# ESP_Updater.net
KiCad netlist of a schematic drawn in EAGLE
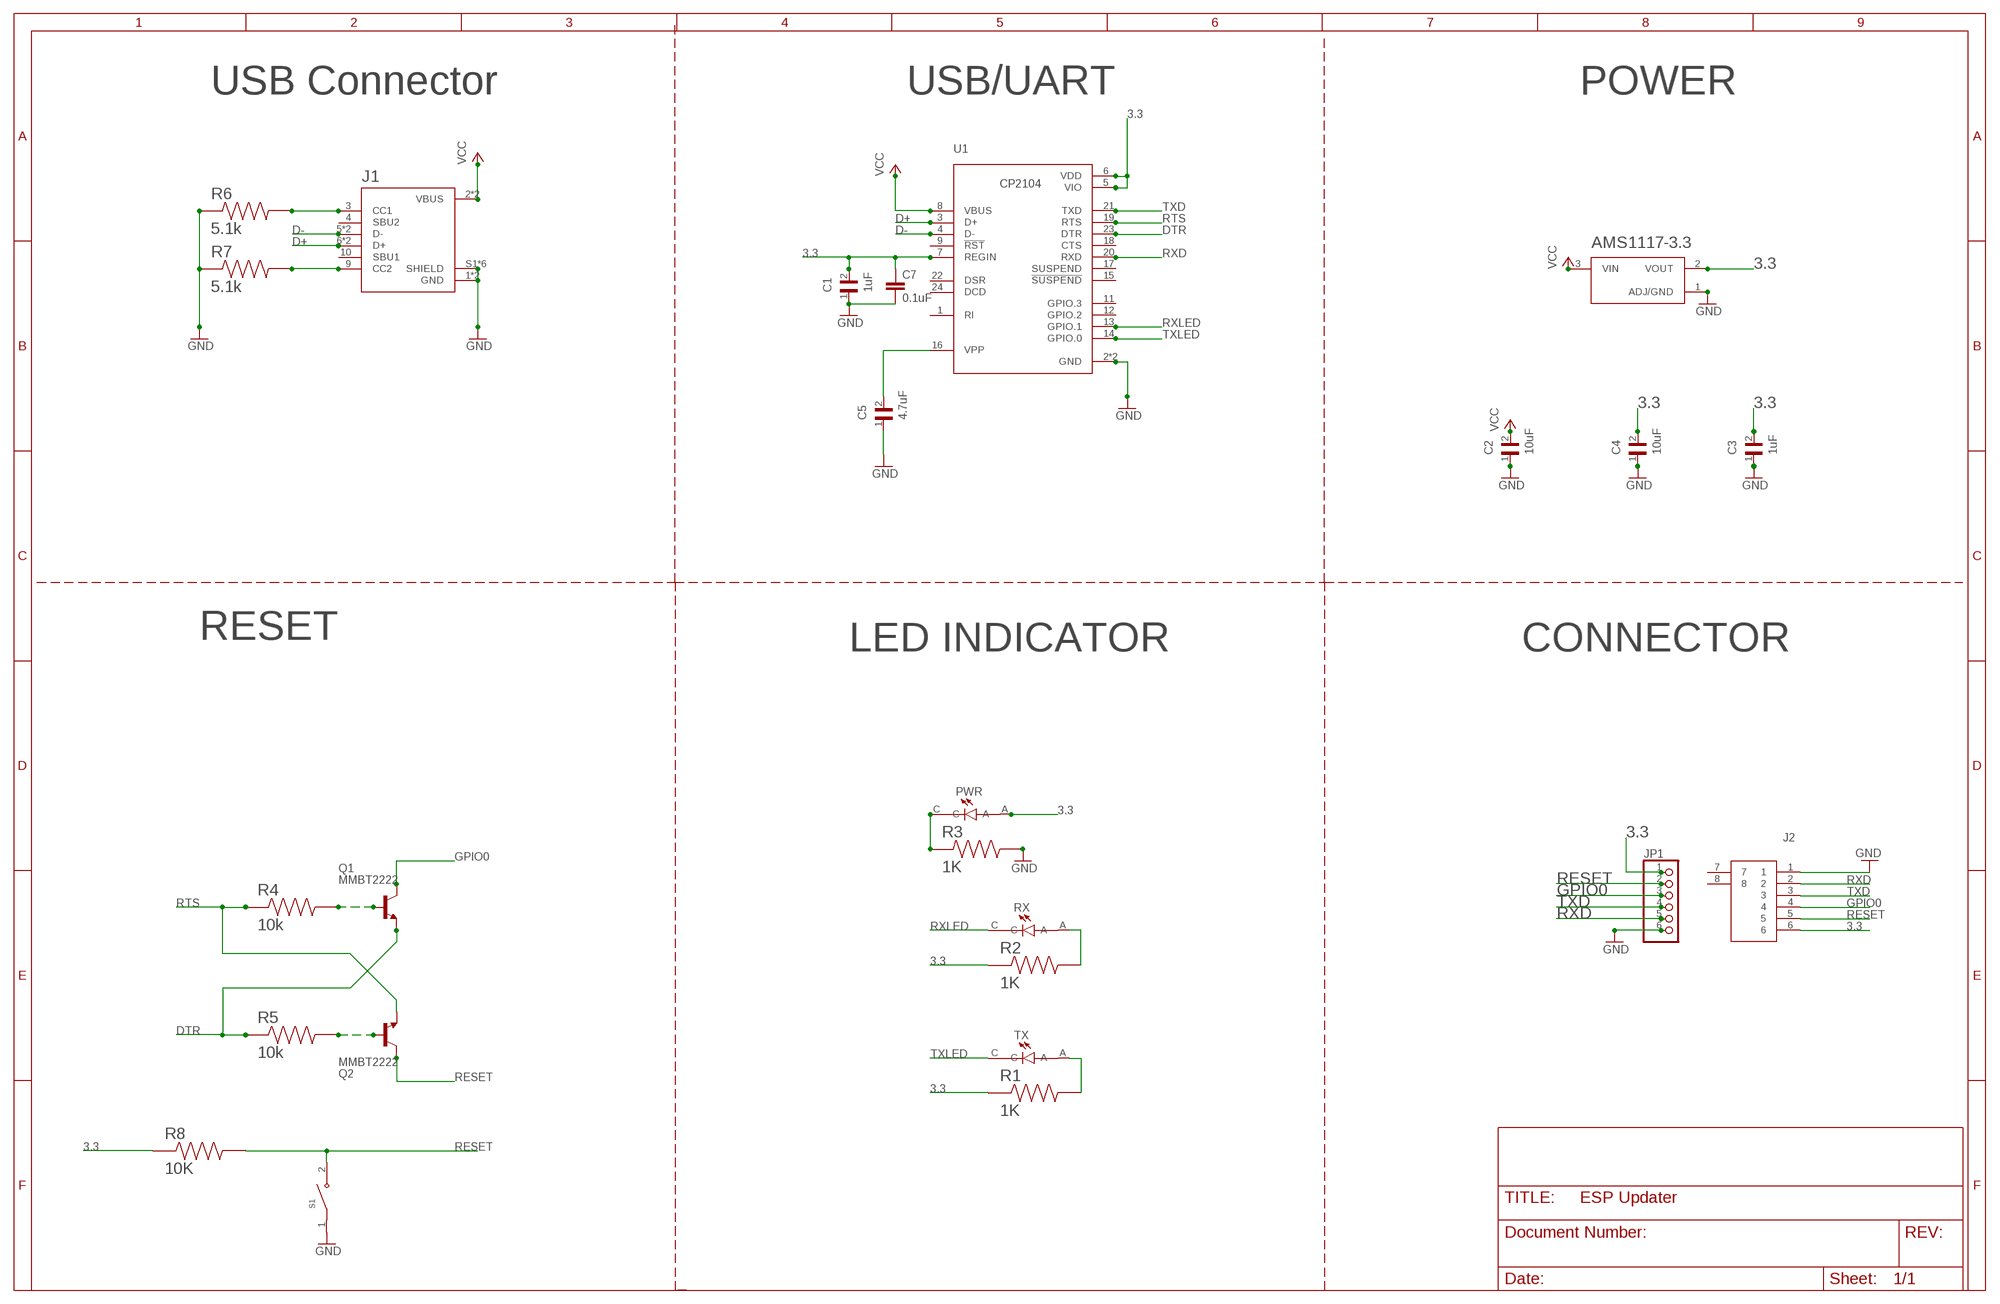
[diagram p0: schematic, sheet 1]

(export (version "E")
  (design (tool "Eeschema 10.0.6"))
  (components
    (comp (ref "C1")
      (value "1uF")
      (footprint "eagle-import:CAPC2012X94N")
      (fields (field (name "MF") "AVX") (field (name "MP") "0805YC103J4T2A"))
      (libsource (lib "eagle-import") (part "0805YC103J4T2A"))
    )
    (comp (ref "C2")
      (value "10uF")
      (footprint "eagle-import:CAPC2012X94N")
      (fields (field (name "MF") "AVX") (field (name "MP") "0805YC103J4T2A"))
      (libsource (lib "eagle-import") (part "0805YC103J4T2A"))
    )
    (comp (ref "C3")
      (value "1uF")
      (footprint "eagle-import:CAPC2012X94N")
      (fields (field (name "MF") "AVX") (field (name "MP") "0805YC103J4T2A"))
      (libsource (lib "eagle-import") (part "0805YC103J4T2A"))
    )
    (comp (ref "C4")
      (value "10uF")
      (footprint "eagle-import:CAPC2012X94N")
      (fields (field (name "MF") "AVX") (field (name "MP") "0805YC103J4T2A"))
      (libsource (lib "eagle-import") (part "0805YC103J4T2A"))
    )
    (comp (ref "C5")
      (value "4.7uF")
      (footprint "eagle-import:CAPC2012X94N")
      (fields (field (name "MF") "AVX") (field (name "MP") "0805YC103J4T2A"))
      (libsource (lib "eagle-import") (part "0805YC103J4T2A"))
    )
    (comp (ref "C7")
      (value "0.1uF")
      (footprint "eagle-import:C0603")
      (libsource (lib "eagle-import") (part "C-EUC0603"))
    )
    (comp (ref "J1")
      (value "DX07S016JA1R1500")
      (footprint "eagle-import:JAE_DX07S016JA1R1500")
      (fields (field (name "MF") "JAE Electronics"))
      (libsource (lib "eagle-import") (part "DX07S016JA1R1500"))
    )
    (comp (ref "J2")
      (value "52852-0670")
      (footprint "eagle-import:528520670")
      (fields (field (name "MOUSER_PART_NUMBER") "538-52852-0670"))
      (libsource (lib "eagle-import") (part "52852-0670"))
    )
    (comp (ref "JP1")
      (value "PINHD-1X6")
      (footprint "eagle-import:1X06")
      (libsource (lib "eagle-import") (part "PINHD-1X6"))
    )
    (comp (ref "PWR")
      (value "SML-LXT0805IW-TR")
      (footprint "eagle-import:LEDC2012X120N")
      (fields (field (name "MF") "Lumex Opto/Components"))
      (libsource (lib "eagle-import") (part "SML-LXT0805IW-TR"))
    )
    (comp (ref "Q1")
      (value "MMBT2222")
      (footprint "eagle-import:SOT23-BEC")
      (fields (field (name "MF") "ON Semiconductor"))
      (libsource (lib "eagle-import") (part "MMBT2222"))
    )
    (comp (ref "Q2")
      (value "MMBT2222")
      (footprint "eagle-import:SOT23-BEC")
      (fields (field (name "MF") "ON Semiconductor"))
      (libsource (lib "eagle-import") (part "MMBT2222"))
    )
    (comp (ref "R1")
      (value "1K")
      (footprint "eagle-import:RESC2012X60N")
      (fields (field (name "MF") "Yageo") (field (name "MP") "RC0805FR-07330RL"))
      (libsource (lib "eagle-import") (part "RC0805FR-07330RL"))
    )
    (comp (ref "R2")
      (value "1K")
      (footprint "eagle-import:RESC2012X60N")
      (fields (field (name "MF") "Yageo") (field (name "MP") "RC0805FR-07330RL"))
      (libsource (lib "eagle-import") (part "RC0805FR-07330RL"))
    )
    (comp (ref "R3")
      (value "1K")
      (footprint "eagle-import:RESC2012X60N")
      (fields (field (name "MF") "Yageo") (field (name "MP") "RC0805FR-07330RL"))
      (libsource (lib "eagle-import") (part "RC0805FR-07330RL"))
    )
    (comp (ref "R4")
      (value "10k")
      (footprint "eagle-import:RESC2012X60N")
      (fields (field (name "MF") "Yageo") (field (name "MP") "RC0805FR-07330RL"))
      (libsource (lib "eagle-import") (part "RC0805FR-07330RL"))
    )
    (comp (ref "R5")
      (value "10k")
      (footprint "eagle-import:RESC2012X60N")
      (fields (field (name "MF") "Yageo") (field (name "MP") "RC0805FR-07330RL"))
      (libsource (lib "eagle-import") (part "RC0805FR-07330RL"))
    )
    (comp (ref "R6")
      (value "5.1k")
      (footprint "eagle-import:RESC2012X60N")
      (fields (field (name "MF") "Yageo") (field (name "MP") "RC0805FR-07330RL"))
      (libsource (lib "eagle-import") (part "RC0805FR-07330RL"))
    )
    (comp (ref "R7")
      (value "5.1k")
      (footprint "eagle-import:RESC2012X60N")
      (fields (field (name "MF") "Yageo") (field (name "MP") "RC0805FR-07330RL"))
      (libsource (lib "eagle-import") (part "RC0805FR-07330RL"))
    )
    (comp (ref "R8")
      (value "10K")
      (footprint "eagle-import:RESC2012X60N")
      (fields (field (name "MF") "Yageo") (field (name "MP") "RC0805FR-07330RL"))
      (libsource (lib "eagle-import") (part "RC0805FR-07330RL"))
    )
    (comp (ref "RX")
      (value "SML-LXT0805IW-TR")
      (footprint "eagle-import:LEDC2012X120N")
      (fields (field (name "MF") "Lumex Opto/Components"))
      (libsource (lib "eagle-import") (part "SML-LXT0805IW-TR"))
    )
    (comp (ref "S1")
      (value "PTS636_SM43J_SMTR_LFS")
      (footprint "eagle-import:SW_PTS636_SM43J_SMTR_LFS")
      (fields (field (name "MF") "C&K") (field (name "MP") "PTS636 SM43J SMTR LFS"))
      (libsource (lib "eagle-import") (part "PTS636_SM43J_SMTR_LFS"))
    )
    (comp (ref "TX")
      (value "SML-LXT0805IW-TR")
      (footprint "eagle-import:LEDC2012X120N")
      (fields (field (name "MF") "Lumex Opto/Components"))
      (libsource (lib "eagle-import") (part "SML-LXT0805IW-TR"))
    )
    (comp (ref "U1")
      (value "CP2104")
      (footprint "eagle-import:QFN50P400X400X80-25N")
      (fields (field (name "MF") "Silicon Labs") (field (name "MP") "CP2104-F03-GM"))
      (libsource (lib "eagle-import") (part "CP2104-F03-GM"))
    )
    (comp (ref "U2")
      (value "AMS1117-3.3")
      (footprint "eagle-import:SOT229P700X180-4N")
      (fields (field (name "MF") "Advanced Monolithic Systems"))
      (libsource (lib "eagle-import") (part "AMS1117-3.3"))
    )
  )
  (nets
    (net (code "1") (name "/3.3") (class "Default")
      (node (ref "C1") (pin "2") (pinfunction "2_2") (pintype "passive"))
      (node (ref "C3") (pin "2") (pinfunction "2_2") (pintype "passive"))
      (node (ref "C4") (pin "2") (pinfunction "2_2") (pintype "passive"))
      (node (ref "C7") (pin "1") (pinfunction "1_1") (pintype "passive"))
      (node (ref "J2") (pin "6") (pinfunction "6_6") (pintype "bidirectional"))
      (node (ref "JP1") (pin "1") (pinfunction "1_1") (pintype "passive"))
      (node (ref "PWR") (pin "A") (pinfunction "A_A") (pintype "passive"))
      (node (ref "R1") (pin "1") (pinfunction "1_1") (pintype "passive"))
      (node (ref "R2") (pin "1") (pinfunction "1_1") (pintype "passive"))
      (node (ref "R8") (pin "1") (pinfunction "1_1") (pintype "passive"))
      (node (ref "U1") (pin "5") (pinfunction "VIO_5") (pintype "power_in"))
      (node (ref "U1") (pin "6") (pinfunction "VDD_6") (pintype "power_in"))
      (node (ref "U1") (pin "7") (pinfunction "REGIN_7") (pintype "input"))
      (node (ref "U2") (pin "2") (pinfunction "VOUT_2") (pintype "output"))
    )
    (net (code "2") (name "/D+") (class "Default")
      (node (ref "J1") (pin "6") (pinfunction "D+_6") (pintype "passive"))
      (node (ref "J1") (pin "7") (pinfunction "D+_7") (pintype "passive"))
      (node (ref "U1") (pin "3") (pinfunction "D+_3") (pintype "bidirectional"))
    )
    (net (code "3") (name "/D-") (class "Default")
      (node (ref "J1") (pin "5") (pinfunction "D-_5") (pintype "passive"))
      (node (ref "J1") (pin "8") (pinfunction "D-_8") (pintype "passive"))
      (node (ref "U1") (pin "4") (pinfunction "D-_4") (pintype "bidirectional"))
    )
    (net (code "4") (name "/DTR") (class "Default")
      (node (ref "Q1") (pin "E") (pinfunction "E_E") (pintype "passive"))
      (node (ref "R5") (pin "1") (pinfunction "1_1") (pintype "passive"))
      (node (ref "U1") (pin "23") (pinfunction "DTR_23") (pintype "output"))
    )
    (net (code "5") (name "/GPIO0") (class "Default")
      (node (ref "J2") (pin "4") (pinfunction "4_4") (pintype "bidirectional"))
      (node (ref "JP1") (pin "3") (pinfunction "3_3") (pintype "passive"))
      (node (ref "Q1") (pin "C") (pinfunction "C_C") (pintype "passive"))
    )
    (net (code "6") (name "/RESET") (class "Default")
      (node (ref "J2") (pin "5") (pinfunction "5_5") (pintype "bidirectional"))
      (node (ref "JP1") (pin "2") (pinfunction "2_2") (pintype "passive"))
      (node (ref "Q2") (pin "C") (pinfunction "C_C") (pintype "passive"))
      (node (ref "R8") (pin "2") (pinfunction "2_2") (pintype "passive"))
      (node (ref "S1") (pin "2") (pinfunction "NO_2") (pintype "passive"))
    )
    (net (code "7") (name "/RTS") (class "Default")
      (node (ref "Q2") (pin "E") (pinfunction "E_E") (pintype "passive"))
      (node (ref "R4") (pin "1") (pinfunction "1_1") (pintype "passive"))
      (node (ref "U1") (pin "19") (pinfunction "RTS_19") (pintype "output"))
    )
    (net (code "8") (name "/RXD") (class "Default")
      (node (ref "J2") (pin "2") (pinfunction "2_2") (pintype "bidirectional"))
      (node (ref "JP1") (pin "5") (pinfunction "5_5") (pintype "passive"))
      (node (ref "U1") (pin "20") (pinfunction "RXD_20") (pintype "input"))
    )
    (net (code "9") (name "/RXLED") (class "Default")
      (node (ref "RX") (pin "C") (pinfunction "C_C") (pintype "passive"))
      (node (ref "U1") (pin "13") (pinfunction "GPIO.1_13") (pintype "bidirectional"))
    )
    (net (code "10") (name "/TXD") (class "Default")
      (node (ref "J2") (pin "3") (pinfunction "3_3") (pintype "bidirectional"))
      (node (ref "JP1") (pin "4") (pinfunction "4_4") (pintype "passive"))
      (node (ref "U1") (pin "21") (pinfunction "TXD_21") (pintype "output"))
    )
    (net (code "11") (name "/TXLED") (class "Default")
      (node (ref "TX") (pin "C") (pinfunction "C_C") (pintype "passive"))
      (node (ref "U1") (pin "14") (pinfunction "GPIO.0_14") (pintype "bidirectional"))
    )
    (net (code "12") (name "GND") (class "Default")
      (node (ref "C1") (pin "1") (pinfunction "1_1") (pintype "passive"))
      (node (ref "C2") (pin "1") (pinfunction "1_1") (pintype "passive"))
      (node (ref "C3") (pin "1") (pinfunction "1_1") (pintype "passive"))
      (node (ref "C4") (pin "1") (pinfunction "1_1") (pintype "passive"))
      (node (ref "C5") (pin "1") (pinfunction "1_1") (pintype "passive"))
      (node (ref "C7") (pin "2") (pinfunction "2_2") (pintype "passive"))
      (node (ref "J1") (pin "1") (pinfunction "GND_1") (pintype "power_in"))
      (node (ref "J1") (pin "12") (pinfunction "GND_12") (pintype "power_in"))
      (node (ref "J1") (pin "S1") (pinfunction "SHIELD_S1") (pintype "passive"))
      (node (ref "J1") (pin "S2") (pinfunction "SHIELD_S2") (pintype "passive"))
      (node (ref "J1") (pin "S3") (pinfunction "SHIELD_S3") (pintype "passive"))
      (node (ref "J1") (pin "S4") (pinfunction "SHIELD_S4") (pintype "passive"))
      (node (ref "J1") (pin "S5") (pinfunction "SHIELD_S5") (pintype "passive"))
      (node (ref "J1") (pin "S6") (pinfunction "SHIELD_S6") (pintype "passive"))
      (node (ref "J2") (pin "1") (pinfunction "1_1") (pintype "bidirectional"))
      (node (ref "JP1") (pin "6") (pinfunction "6_6") (pintype "passive"))
      (node (ref "R3") (pin "2") (pinfunction "2_2") (pintype "passive"))
      (node (ref "R6") (pin "1") (pinfunction "1_1") (pintype "passive"))
      (node (ref "R7") (pin "1") (pinfunction "1_1") (pintype "passive"))
      (node (ref "S1") (pin "1") (pinfunction "COM_1") (pintype "passive"))
      (node (ref "U1") (pin "2") (pinfunction "GND_2") (pintype "power_in"))
      (node (ref "U1") (pin "25") (pinfunction "GND_25") (pintype "power_in"))
      (node (ref "U2") (pin "1") (pinfunction "ADJ/GND_1") (pintype "power_in"))
    )
    (net (code "13") (name "Net-(J1-CC1)") (class "Default")
      (node (ref "J1") (pin "3") (pinfunction "CC1_3") (pintype "passive"))
      (node (ref "R6") (pin "2") (pinfunction "2_2") (pintype "passive"))
    )
    (net (code "14") (name "Net-(J1-CC2)") (class "Default")
      (node (ref "J1") (pin "9") (pinfunction "CC2_9") (pintype "passive"))
      (node (ref "R7") (pin "2") (pinfunction "2_2") (pintype "passive"))
    )
    (net (code "15") (name "Net-(PWR-PadC)") (class "Default")
      (node (ref "PWR") (pin "C") (pinfunction "C_C") (pintype "passive"))
      (node (ref "R3") (pin "1") (pinfunction "1_1") (pintype "passive"))
    )
    (net (code "16") (name "Net-(Q1-PadB)") (class "Default")
      (node (ref "Q1") (pin "B") (pinfunction "B_B") (pintype "passive"))
      (node (ref "R4") (pin "2") (pinfunction "2_2") (pintype "passive"))
    )
    (net (code "17") (name "Net-(Q2-PadB)") (class "Default")
      (node (ref "Q2") (pin "B") (pinfunction "B_B") (pintype "passive"))
      (node (ref "R5") (pin "2") (pinfunction "2_2") (pintype "passive"))
    )
    (net (code "18") (name "Net-(R1-Pad2)") (class "Default")
      (node (ref "R1") (pin "2") (pinfunction "2_2") (pintype "passive"))
      (node (ref "TX") (pin "A") (pinfunction "A_A") (pintype "passive"))
    )
    (net (code "19") (name "Net-(R2-Pad2)") (class "Default")
      (node (ref "R2") (pin "2") (pinfunction "2_2") (pintype "passive"))
      (node (ref "RX") (pin "A") (pinfunction "A_A") (pintype "passive"))
    )
    (net (code "20") (name "Net-(U1-VPP)") (class "Default")
      (node (ref "C5") (pin "2") (pinfunction "2_2") (pintype "passive"))
      (node (ref "U1") (pin "16") (pinfunction "VPP_16") (pintype "passive"))
    )
    (net (code "21") (name "VCC") (class "Default")
      (node (ref "C2") (pin "2") (pinfunction "2_2") (pintype "passive"))
      (node (ref "J1") (pin "11") (pinfunction "VBUS_11") (pintype "power_in"))
      (node (ref "J1") (pin "2") (pinfunction "VBUS_2") (pintype "power_in"))
      (node (ref "U1") (pin "8") (pinfunction "VBUS_8") (pintype "input"))
      (node (ref "U2") (pin "3") (pinfunction "VIN_3") (pintype "input"))
    )
    (net (code "22") (name "unconnected-(J1-SBU1-Pad10)") (class "Default")
      (node (ref "J1") (pin "10") (pinfunction "SBU1_10") (pintype "passive"))
    )
    (net (code "23") (name "unconnected-(J1-SBU2-Pad4)") (class "Default")
      (node (ref "J1") (pin "4") (pinfunction "SBU2_4") (pintype "passive"))
    )
    (net (code "24") (name "unconnected-(J2-Pad7)") (class "Default")
      (node (ref "J2") (pin "7") (pinfunction "7_7") (pintype "bidirectional"))
    )
    (net (code "25") (name "unconnected-(J2-Pad8)") (class "Default")
      (node (ref "J2") (pin "8") (pinfunction "8_8") (pintype "bidirectional"))
    )
    (net (code "26") (name "unconnected-(U1-CTS-Pad18)") (class "Default")
      (node (ref "U1") (pin "18") (pinfunction "CTS_18") (pintype "input"))
    )
    (net (code "27") (name "unconnected-(U1-DCD-Pad24)") (class "Default")
      (node (ref "U1") (pin "24") (pinfunction "DCD_24") (pintype "input"))
    )
    (net (code "28") (name "unconnected-(U1-DSR-Pad22)") (class "Default")
      (node (ref "U1") (pin "22") (pinfunction "DSR_22") (pintype "input"))
    )
    (net (code "29") (name "unconnected-(U1-GPIO.2-Pad12)") (class "Default")
      (node (ref "U1") (pin "12") (pinfunction "GPIO.2_12") (pintype "bidirectional"))
    )
    (net (code "30") (name "unconnected-(U1-GPIO.3-Pad11)") (class "Default")
      (node (ref "U1") (pin "11") (pinfunction "GPIO.3_11") (pintype "bidirectional"))
    )
    (net (code "31") (name "unconnected-(U1-RI-Pad1)") (class "Default")
      (node (ref "U1") (pin "1") (pinfunction "RI_1") (pintype "input"))
    )
    (net (code "32") (name "unconnected-(U1-SUSPEND-Pad17)") (class "Default")
      (node (ref "U1") (pin "17") (pinfunction "SUSPEND_17") (pintype "output"))
    )
    (net (code "33") (name "unconnected-(U1-~{RST}-Pad9)") (class "Default")
      (node (ref "U1") (pin "9") (pinfunction "~{RST}_9") (pintype "input"))
    )
    (net (code "34") (name "unconnected-(U1-~{SUSPEND}-Pad15)") (class "Default")
      (node (ref "U1") (pin "15") (pinfunction "~{SUSPEND}_15") (pintype "output"))
    )
  )
)
